# TSOC-USBUART1-3-1.net
KiCad netlist of a schematic drawn in EAGLE
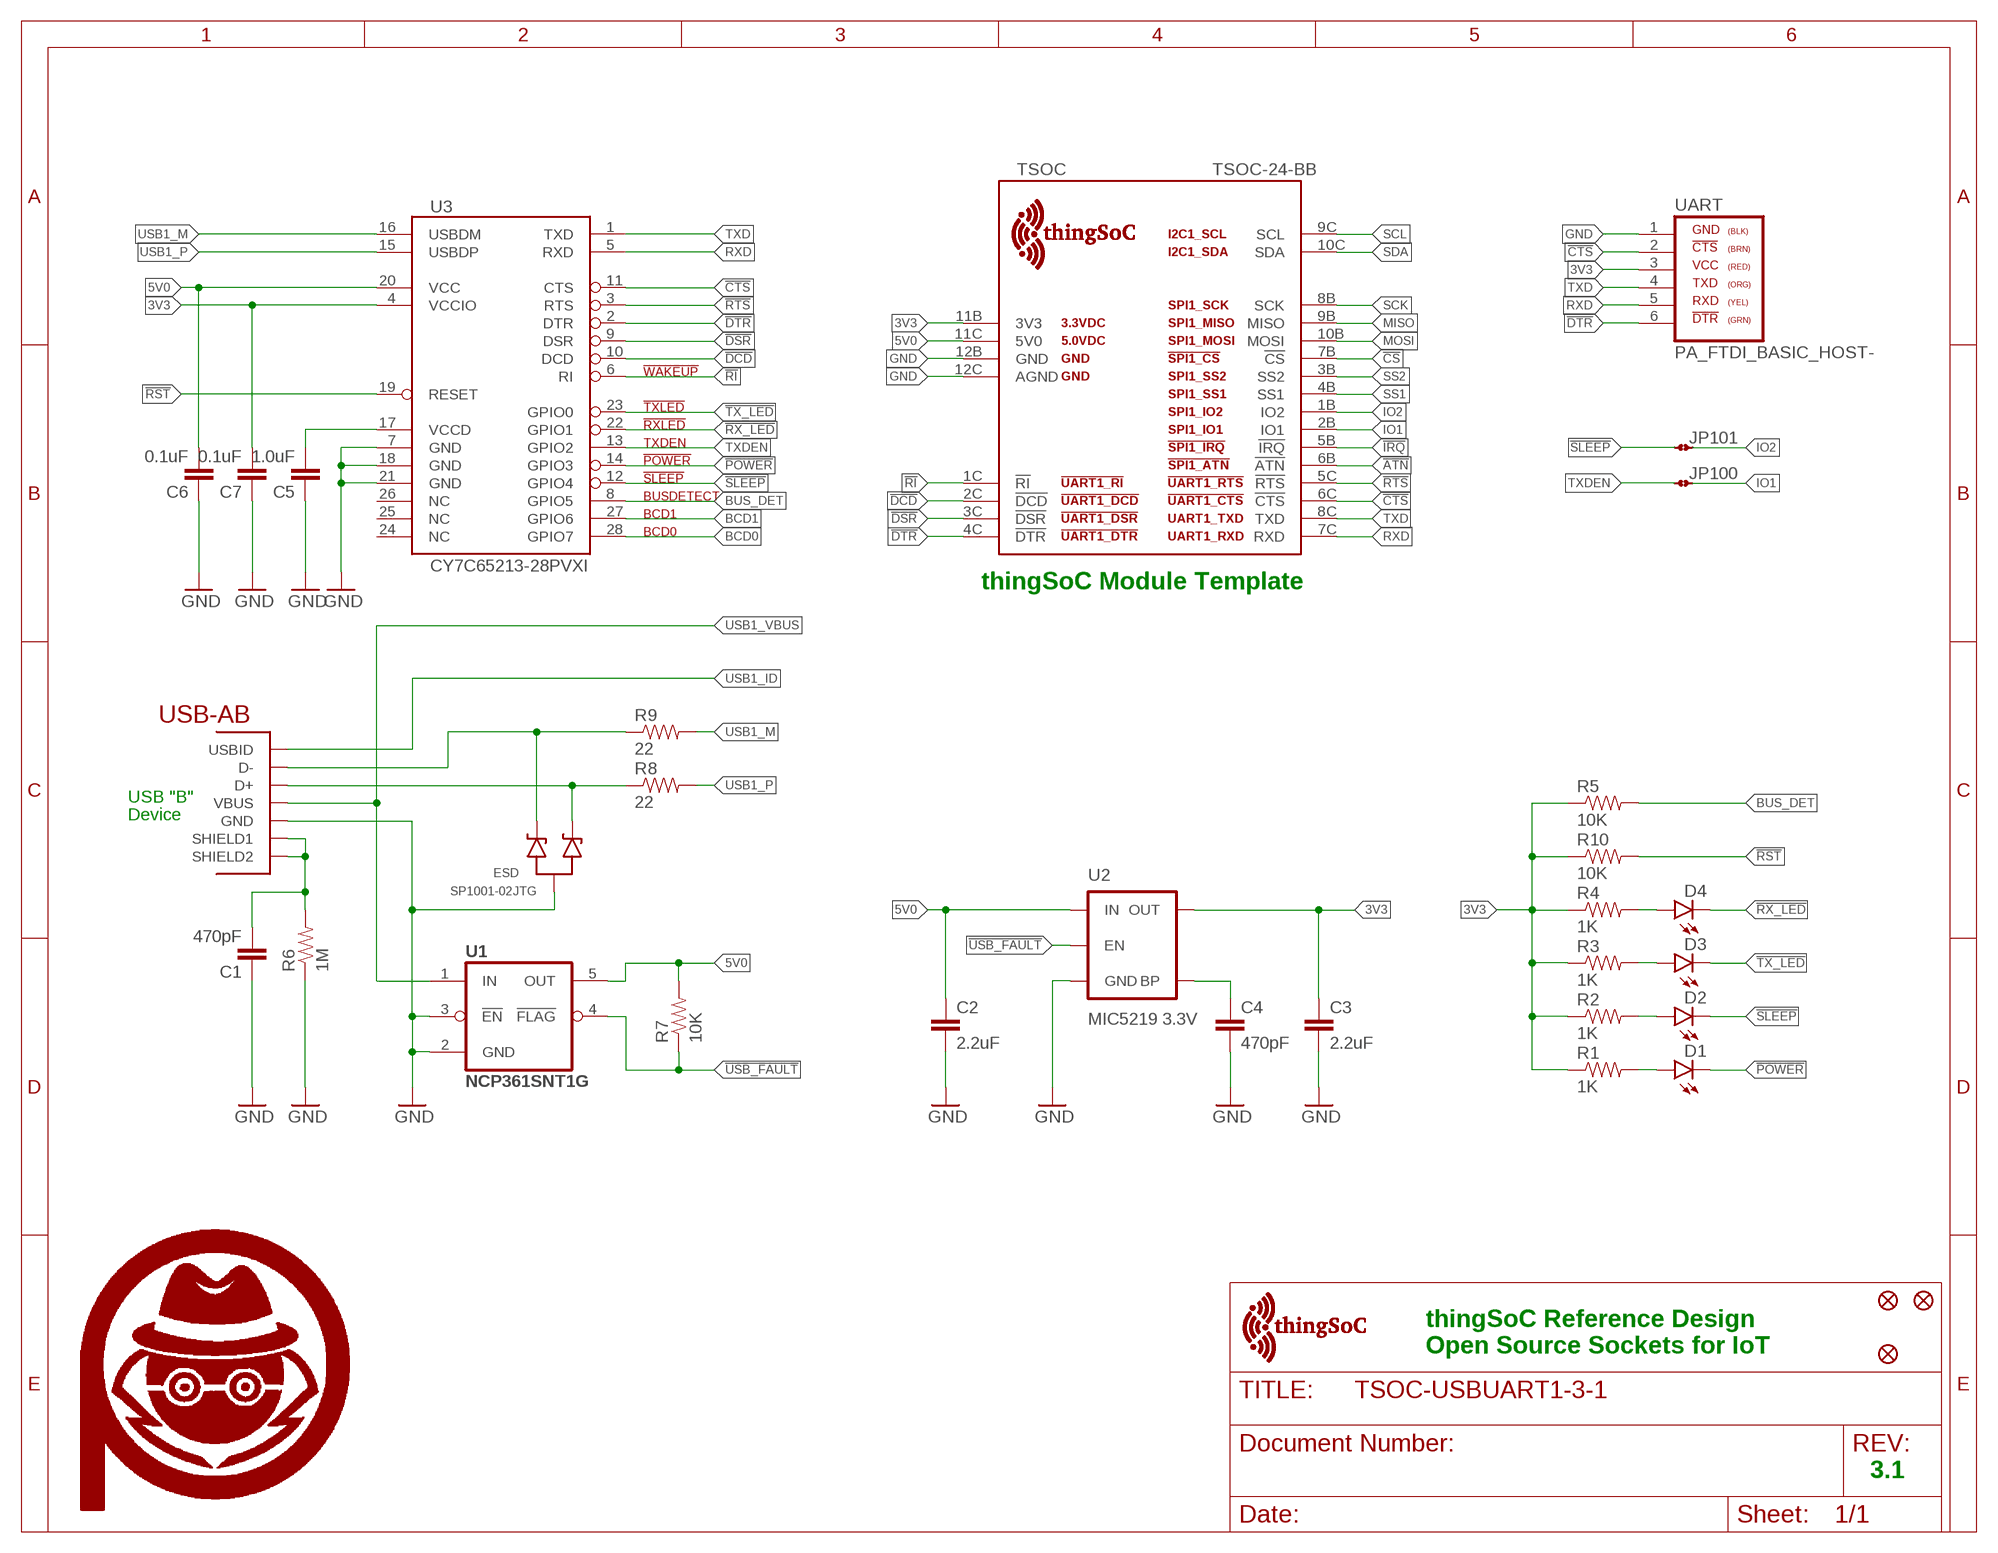
[diagram p0: schematic, sheet 1]

(export (version "E")
  (design (tool "Eeschema 10.0.6"))
  (components
    (comp (ref "C1")
      (value "470pF")
      (footprint "eagle-import:0603-CAP")
      (libsource (lib "eagle-import") (part "CAP0603-CAP"))
    )
    (comp (ref "C2")
      (value "2.2uF")
      (footprint "eagle-import:0603-CAP")
      (libsource (lib "eagle-import") (part "CAP0603-CAP"))
    )
    (comp (ref "C3")
      (value "2.2uF")
      (footprint "eagle-import:0603-CAP")
      (libsource (lib "eagle-import") (part "CAP0603-CAP"))
    )
    (comp (ref "C4")
      (value "470pF")
      (footprint "eagle-import:0603-CAP")
      (libsource (lib "eagle-import") (part "CAP0603-CAP"))
    )
    (comp (ref "C5")
      (value "1.0uF")
      (footprint "eagle-import:0603-CAP")
      (libsource (lib "eagle-import") (part "CAP0603-CAP"))
    )
    (comp (ref "C6")
      (value "0.1uF")
      (footprint "eagle-import:0603-CAP")
      (libsource (lib "eagle-import") (part "CAP0603-CAP"))
    )
    (comp (ref "C7")
      (value "0.1uF")
      (footprint "eagle-import:0603-CAP")
      (libsource (lib "eagle-import") (part "CAP0603-CAP"))
    )
    (comp (ref "D1")
      (value "LED0603")
      (footprint "eagle-import:LED-0603")
      (libsource (lib "eagle-import") (part "LED0603"))
    )
    (comp (ref "D2")
      (value "LED0603")
      (footprint "eagle-import:LED-0603")
      (libsource (lib "eagle-import") (part "LED0603"))
    )
    (comp (ref "D3")
      (value "LED0603")
      (footprint "eagle-import:LED-0603")
      (libsource (lib "eagle-import") (part "LED0603"))
    )
    (comp (ref "D4")
      (value "LED0603")
      (footprint "eagle-import:LED-0603")
      (libsource (lib "eagle-import") (part "LED0603"))
    )
    (comp (ref "ESD")
      (value "SP1001-02JTG")
      (footprint "eagle-import:SC70-3")
      (libsource (lib "eagle-import") (part "SP1001-02JTG"))
    )
    (comp (ref "FID1")
      (value "FIDUCIAL1.5X3")
      (footprint "eagle-import:FIDUCIAL-1.5X3")
      (libsource (lib "eagle-import") (part "FIDUCIAL1.5X3"))
    )
    (comp (ref "FID2")
      (value "FIDUCIAL1.5X3")
      (footprint "eagle-import:FIDUCIAL-1.5X3")
      (libsource (lib "eagle-import") (part "FIDUCIAL1.5X3"))
    )
    (comp (ref "FID3")
      (value "FIDUCIAL1.5X3")
      (footprint "eagle-import:FIDUCIAL-1.5X3")
      (libsource (lib "eagle-import") (part "FIDUCIAL1.5X3"))
    )
    (comp (ref "JP100")
      (value "JMP-2-NO")
      (footprint "eagle-import:JMP-2-NO")
      (libsource (lib "eagle-import") (part "JMP-2-NO"))
    )
    (comp (ref "JP101")
      (value "JMP-2-NO")
      (footprint "eagle-import:JMP-2-NO")
      (libsource (lib "eagle-import") (part "JMP-2-NO"))
    )
    (comp (ref "R1")
      (value "1K")
      (footprint "eagle-import:0603-RES")
      (libsource (lib "eagle-import") (part "RESISTOR0603-RES"))
    )
    (comp (ref "R2")
      (value "1K")
      (footprint "eagle-import:0603-RES")
      (libsource (lib "eagle-import") (part "RESISTOR0603-RES"))
    )
    (comp (ref "R3")
      (value "1K")
      (footprint "eagle-import:0603-RES")
      (libsource (lib "eagle-import") (part "RESISTOR0603-RES"))
    )
    (comp (ref "R4")
      (value "1K")
      (footprint "eagle-import:0603-RES")
      (libsource (lib "eagle-import") (part "RESISTOR0603-RES"))
    )
    (comp (ref "R5")
      (value "10K")
      (footprint "eagle-import:0603-RES")
      (libsource (lib "eagle-import") (part "RESISTOR0603-RES"))
    )
    (comp (ref "R6")
      (value "1M")
      (footprint "eagle-import:0603-RES")
      (libsource (lib "eagle-import") (part "RESISTOR0603-RES"))
    )
    (comp (ref "R7")
      (value "10K")
      (footprint "eagle-import:0603-RES")
      (libsource (lib "eagle-import") (part "RESISTOR0603-RES"))
    )
    (comp (ref "R8")
      (value "22")
      (footprint "eagle-import:0603-RES")
      (libsource (lib "eagle-import") (part "RESISTOR0603-RES"))
    )
    (comp (ref "R9")
      (value "22")
      (footprint "eagle-import:0603-RES")
      (libsource (lib "eagle-import") (part "RESISTOR0603-RES"))
    )
    (comp (ref "R10")
      (value "10K")
      (footprint "eagle-import:0603-RES")
      (libsource (lib "eagle-import") (part "RESISTOR0603-RES"))
    )
    (comp (ref "TSOC")
      (value "TSOC-24-BB")
      (footprint "eagle-import:TSOC-BB-S24")
      (libsource (lib "eagle-import") (part "TSOC-24-BB"))
    )
    (comp (ref "U$2")
      (value "TSOC-LOGO-MED")
      (footprint "eagle-import:TSOC-LOGO-MED")
      (libsource (lib "eagle-import") (part "TSOC-LOGO-MED"))
    )
    (comp (ref "U$3")
      (value "PA_LOGO_SYMMED")
      (footprint "eagle-import:PA_LOGO_AGENT_MED_SYM")
      (libsource (lib "eagle-import") (part "PA_LOGO_SYMMED"))
    )
    (comp (ref "U$100")
      (value "PA_LOGO_SYMMED")
      (footprint "eagle-import:PA_LOGO_AGENT_MED_SYM")
      (libsource (lib "eagle-import") (part "PA_LOGO_SYMMED"))
    )
    (comp (ref "U$101")
      (value "TSOC-LOGO-MED")
      (footprint "eagle-import:TSOC-LOGO-MED")
      (libsource (lib "eagle-import") (part "TSOC-LOGO-MED"))
    )
    (comp (ref "U1")
      (value "NCP361SNT1G")
      (footprint "eagle-import:SOP95P275X110-5N")
      (libsource (lib "eagle-import") (part "NCP361SNT1G"))
    )
    (comp (ref "U2")
      (value "MIC5219 3.3V")
      (footprint "eagle-import:SOT23-5")
      (libsource (lib "eagle-import") (part "V_REG_MIC52193.3V"))
    )
    (comp (ref "U3")
      (value "CY7C65213-28PVXI")
      (footprint "eagle-import:SSOP28DB")
      (libsource (lib "eagle-import") (part "CY7C65213-28PVXI"))
    )
    (comp (ref "UART")
      (value "PA_FTDI_BASIC_HOST-")
      (footprint "eagle-import:PA_FTDI_M5X1")
      (libsource (lib "eagle-import") (part "PA_FTDI_BASIC_HOST-"))
    )
    (comp (ref "USB1")
      (value "USB_AB")
      (footprint "eagle-import:USB-AB-MICRO-SMD")
      (libsource (lib "eagle-import") (part "USB_AB"))
    )
  )
  (nets
    (net (code "1") (name "/~{ATN}") (class "Default")
      (node (ref "TSOC") (pin "6B") (pinfunction "~{ATN}_6B") (pintype "bidirectional"))
    )
    (net (code "2") (name "/~{CS}") (class "Default")
      (node (ref "TSOC") (pin "7B") (pinfunction "~{CS}_7B") (pintype "bidirectional"))
    )
    (net (code "3") (name "/~{CTS}") (class "Default")
      (node (ref "TSOC") (pin "6C") (pinfunction "~{CTS}_6C") (pintype "bidirectional"))
      (node (ref "U3") (pin "11") (pinfunction "CTS_11") (pintype "input"))
      (node (ref "UART") (pin "2") (pinfunction "2_2") (pintype "passive"))
    )
    (net (code "4") (name "/~{DCD}") (class "Default")
      (node (ref "TSOC") (pin "2C") (pinfunction "~{DCD}_2C") (pintype "bidirectional"))
      (node (ref "U3") (pin "10") (pinfunction "DCD_10") (pintype "input"))
    )
    (net (code "5") (name "/~{DSR}") (class "Default")
      (node (ref "TSOC") (pin "3C") (pinfunction "~{DSR}_3C") (pintype "bidirectional"))
      (node (ref "U3") (pin "9") (pinfunction "DSR_9") (pintype "input"))
    )
    (net (code "6") (name "/~{DTR}") (class "Default")
      (node (ref "TSOC") (pin "4C") (pinfunction "~{DTR}_4C") (pintype "bidirectional"))
      (node (ref "U3") (pin "2") (pinfunction "DTR_2") (pintype "output"))
      (node (ref "UART") (pin "6") (pinfunction "6_6") (pintype "passive"))
    )
    (net (code "7") (name "/~{IRQ}") (class "Default")
      (node (ref "TSOC") (pin "5B") (pinfunction "~{IRQ}_5B") (pintype "bidirectional"))
    )
    (net (code "8") (name "/~{POWER}") (class "Default")
      (node (ref "D1") (pin "C") (pinfunction "C_C") (pintype "passive"))
      (node (ref "U3") (pin "14") (pinfunction "GPIO3_14") (pintype "output"))
    )
    (net (code "9") (name "/~{RI}") (class "Default")
      (node (ref "TSOC") (pin "1C") (pinfunction "~{RI}_1C") (pintype "bidirectional"))
      (node (ref "U3") (pin "6") (pinfunction "RI_6") (pintype "input"))
    )
    (net (code "10") (name "/~{RST}") (class "Default")
      (node (ref "R10") (pin "2") (pinfunction "2_2") (pintype "passive"))
      (node (ref "U3") (pin "19") (pinfunction "RESET_19") (pintype "input"))
    )
    (net (code "11") (name "/~{RTS}") (class "Default")
      (node (ref "TSOC") (pin "5C") (pinfunction "~{RTS}_5C") (pintype "bidirectional"))
      (node (ref "U3") (pin "3") (pinfunction "RTS_3") (pintype "output"))
    )
    (net (code "12") (name "/~{RX_LED}") (class "Default")
      (node (ref "D4") (pin "C") (pinfunction "C_C") (pintype "passive"))
      (node (ref "U3") (pin "22") (pinfunction "GPIO1_22") (pintype "output"))
    )
    (net (code "13") (name "/~{SLEEP}") (class "Default")
      (node (ref "D2") (pin "C") (pinfunction "C_C") (pintype "passive"))
      (node (ref "JP101") (pin "1") (pinfunction "1_1") (pintype "passive"))
      (node (ref "U3") (pin "12") (pinfunction "GPIO4_12") (pintype "input"))
    )
    (net (code "14") (name "/~{TX_LED}") (class "Default")
      (node (ref "D3") (pin "C") (pinfunction "C_C") (pintype "passive"))
      (node (ref "U3") (pin "23") (pinfunction "GPIO0_23") (pintype "output"))
    )
    (net (code "15") (name "/~{USB_FAULT}") (class "Default")
      (node (ref "R7") (pin "1") (pinfunction "1_1") (pintype "passive"))
      (node (ref "U1") (pin "4") (pinfunction "~{FLAG}_4") (pintype "input"))
      (node (ref "U2") (pin "3") (pinfunction "EN_3") (pintype "input"))
    )
    (net (code "16") (name "3V3") (class "Default")
      (node (ref "C3") (pin "1") (pinfunction "1_1") (pintype "passive"))
      (node (ref "C7") (pin "2") (pinfunction "2_2") (pintype "passive"))
      (node (ref "R1") (pin "1") (pinfunction "1_1") (pintype "passive"))
      (node (ref "R10") (pin "1") (pinfunction "1_1") (pintype "passive"))
      (node (ref "R2") (pin "1") (pinfunction "1_1") (pintype "passive"))
      (node (ref "R3") (pin "1") (pinfunction "1_1") (pintype "passive"))
      (node (ref "R4") (pin "1") (pinfunction "1_1") (pintype "passive"))
      (node (ref "R5") (pin "1") (pinfunction "1_1") (pintype "passive"))
      (node (ref "TSOC") (pin "11B") (pinfunction "3V3_11B") (pintype "bidirectional"))
      (node (ref "U2") (pin "5") (pinfunction "OUT_5") (pintype "passive"))
      (node (ref "U3") (pin "4") (pinfunction "VCCIO_4") (pintype "power_in"))
      (node (ref "UART") (pin "3") (pinfunction "3_3") (pintype "passive"))
    )
    (net (code "17") (name "5V0") (class "Default")
      (node (ref "C2") (pin "1") (pinfunction "1_1") (pintype "passive"))
      (node (ref "C6") (pin "2") (pinfunction "2_2") (pintype "passive"))
      (node (ref "R7") (pin "2") (pinfunction "2_2") (pintype "passive"))
      (node (ref "TSOC") (pin "11C") (pinfunction "5V0_11C") (pintype "bidirectional"))
      (node (ref "U1") (pin "5") (pinfunction "OUT_5") (pintype "output"))
      (node (ref "U2") (pin "1") (pinfunction "IN_1") (pintype "input"))
      (node (ref "U3") (pin "20") (pinfunction "VCC_20") (pintype "power_in"))
    )
    (net (code "18") (name "BCD0") (class "Default")
      (node (ref "U3") (pin "28") (pinfunction "GPIO7_28") (pintype "output"))
    )
    (net (code "19") (name "BCD1") (class "Default")
      (node (ref "U3") (pin "27") (pinfunction "GPIO6_27") (pintype "output"))
    )
    (net (code "20") (name "BUS_DET") (class "Default")
      (node (ref "R5") (pin "2") (pinfunction "2_2") (pintype "passive"))
      (node (ref "U3") (pin "8") (pinfunction "GPIO5_8") (pintype "input"))
    )
    (net (code "21") (name "GND") (class "Default")
      (node (ref "C1") (pin "1") (pinfunction "1_1") (pintype "passive"))
      (node (ref "C2") (pin "2") (pinfunction "2_2") (pintype "passive"))
      (node (ref "C3") (pin "2") (pinfunction "2_2") (pintype "passive"))
      (node (ref "C4") (pin "2") (pinfunction "2_2") (pintype "passive"))
      (node (ref "C5") (pin "1") (pinfunction "1_1") (pintype "passive"))
      (node (ref "C6") (pin "1") (pinfunction "1_1") (pintype "passive"))
      (node (ref "C7") (pin "1") (pinfunction "1_1") (pintype "passive"))
      (node (ref "ESD") (pin "3") (pinfunction "A_3") (pintype "passive"))
      (node (ref "R6") (pin "1") (pinfunction "1_1") (pintype "passive"))
      (node (ref "TSOC") (pin "12B") (pinfunction "GND_12B") (pintype "bidirectional"))
      (node (ref "TSOC") (pin "12C") (pinfunction "AGND_12C") (pintype "bidirectional"))
      (node (ref "U1") (pin "2") (pinfunction "GND_2") (pintype "passive"))
      (node (ref "U1") (pin "3") (pinfunction "~{EN}_3") (pintype "input"))
      (node (ref "U2") (pin "2") (pinfunction "GND_2") (pintype "input"))
      (node (ref "U3") (pin "18") (pinfunction "GND_18") (pintype "power_in"))
      (node (ref "U3") (pin "21") (pinfunction "GND_21") (pintype "power_in"))
      (node (ref "U3") (pin "7") (pinfunction "GND_7") (pintype "power_in"))
      (node (ref "UART") (pin "1") (pinfunction "1_1") (pintype "passive"))
      (node (ref "USB1") (pin "GND") (pinfunction "GND_GND") (pintype "bidirectional"))
    )
    (net (code "22") (name "IO1") (class "Default")
      (node (ref "JP100") (pin "2") (pinfunction "2_2") (pintype "passive"))
      (node (ref "TSOC") (pin "2B") (pinfunction "IO1_2B") (pintype "bidirectional"))
    )
    (net (code "23") (name "IO2") (class "Default")
      (node (ref "JP101") (pin "2") (pinfunction "2_2") (pintype "passive"))
      (node (ref "TSOC") (pin "1B") (pinfunction "IO2_1B") (pintype "bidirectional"))
    )
    (net (code "24") (name "MISO") (class "Default")
      (node (ref "TSOC") (pin "9B") (pinfunction "MISO_9B") (pintype "bidirectional"))
    )
    (net (code "25") (name "MOSI") (class "Default")
      (node (ref "TSOC") (pin "10B") (pinfunction "MOSI_10B") (pintype "bidirectional"))
    )
    (net (code "26") (name "Net-(C1-Pad2)") (class "Default")
      (node (ref "C1") (pin "2") (pinfunction "2_2") (pintype "passive"))
      (node (ref "R6") (pin "2") (pinfunction "2_2") (pintype "passive"))
      (node (ref "USB1") (pin "SHIELD1") (pinfunction "SHIELD1_SHIELD1") (pintype "bidirectional"))
      (node (ref "USB1") (pin "SHIELD2") (pinfunction "SHIELD2_SHIELD2") (pintype "bidirectional"))
    )
    (net (code "27") (name "Net-(D1-PadA)") (class "Default")
      (node (ref "D1") (pin "A") (pinfunction "A_A") (pintype "passive"))
      (node (ref "R1") (pin "2") (pinfunction "2_2") (pintype "passive"))
    )
    (net (code "28") (name "Net-(D2-PadA)") (class "Default")
      (node (ref "D2") (pin "A") (pinfunction "A_A") (pintype "passive"))
      (node (ref "R2") (pin "2") (pinfunction "2_2") (pintype "passive"))
    )
    (net (code "29") (name "Net-(D3-PadA)") (class "Default")
      (node (ref "D3") (pin "A") (pinfunction "A_A") (pintype "passive"))
      (node (ref "R3") (pin "2") (pinfunction "2_2") (pintype "passive"))
    )
    (net (code "30") (name "Net-(D4-PadA)") (class "Default")
      (node (ref "D4") (pin "A") (pinfunction "A_A") (pintype "passive"))
      (node (ref "R4") (pin "2") (pinfunction "2_2") (pintype "passive"))
    )
    (net (code "31") (name "Net-(ESD-C1)") (class "Default")
      (node (ref "ESD") (pin "1") (pinfunction "C1_1") (pintype "passive"))
      (node (ref "R8") (pin "1") (pinfunction "1_1") (pintype "passive"))
      (node (ref "USB1") (pin "D+") (pinfunction "D+_D+") (pintype "bidirectional"))
    )
    (net (code "32") (name "Net-(ESD-C2)") (class "Default")
      (node (ref "ESD") (pin "2") (pinfunction "C2_2") (pintype "passive"))
      (node (ref "R9") (pin "1") (pinfunction "1_1") (pintype "passive"))
      (node (ref "USB1") (pin "D-") (pinfunction "D-_D-") (pintype "bidirectional"))
    )
    (net (code "33") (name "Net-(U2-BP)") (class "Default")
      (node (ref "C4") (pin "1") (pinfunction "1_1") (pintype "passive"))
      (node (ref "U2") (pin "4") (pinfunction "BP_4") (pintype "input"))
    )
    (net (code "34") (name "Net-(U3-VCCD)") (class "Default")
      (node (ref "C5") (pin "2") (pinfunction "2_2") (pintype "passive"))
      (node (ref "U3") (pin "17") (pinfunction "VCCD_17") (pintype "power_in"))
    )
    (net (code "35") (name "RXD") (class "Default")
      (node (ref "TSOC") (pin "7C") (pinfunction "RXD_7C") (pintype "bidirectional"))
      (node (ref "U3") (pin "5") (pinfunction "RXD_5") (pintype "input"))
      (node (ref "UART") (pin "5") (pinfunction "5_5") (pintype "passive"))
    )
    (net (code "36") (name "SCK") (class "Default")
      (node (ref "TSOC") (pin "8B") (pinfunction "SCK_8B") (pintype "bidirectional"))
    )
    (net (code "37") (name "SCL") (class "Default")
      (node (ref "TSOC") (pin "9C") (pinfunction "SCL_9C") (pintype "bidirectional"))
    )
    (net (code "38") (name "SDA") (class "Default")
      (node (ref "TSOC") (pin "10C") (pinfunction "SDA_10C") (pintype "bidirectional"))
    )
    (net (code "39") (name "SS1") (class "Default")
      (node (ref "TSOC") (pin "4B") (pinfunction "SS1_4B") (pintype "bidirectional"))
    )
    (net (code "40") (name "SS2") (class "Default")
      (node (ref "TSOC") (pin "3B") (pinfunction "SS2_3B") (pintype "bidirectional"))
    )
    (net (code "41") (name "TXD") (class "Default")
      (node (ref "TSOC") (pin "8C") (pinfunction "TXD_8C") (pintype "bidirectional"))
      (node (ref "U3") (pin "1") (pinfunction "TXD_1") (pintype "output"))
      (node (ref "UART") (pin "4") (pinfunction "4_4") (pintype "passive"))
    )
    (net (code "42") (name "TXDEN") (class "Default")
      (node (ref "JP100") (pin "1") (pinfunction "1_1") (pintype "passive"))
      (node (ref "U3") (pin "13") (pinfunction "GPIO2_13") (pintype "output"))
    )
    (net (code "43") (name "USB1_ID") (class "Default")
      (node (ref "USB1") (pin "ID") (pinfunction "USBID_ID") (pintype "bidirectional"))
    )
    (net (code "44") (name "USB1_M") (class "Default")
      (node (ref "R9") (pin "2") (pinfunction "2_2") (pintype "passive"))
      (node (ref "U3") (pin "16") (pinfunction "USBDM_16") (pintype "bidirectional"))
    )
    (net (code "45") (name "USB1_P") (class "Default")
      (node (ref "R8") (pin "2") (pinfunction "2_2") (pintype "passive"))
      (node (ref "U3") (pin "15") (pinfunction "USBDP_15") (pintype "bidirectional"))
    )
    (net (code "46") (name "USB1_VBUS") (class "Default")
      (node (ref "U1") (pin "1") (pinfunction "IN_1") (pintype "power_in"))
      (node (ref "USB1") (pin "VBUS") (pinfunction "VBUS_VBUS") (pintype "bidirectional"))
    )
    (net (code "47") (name "unconnected-(U3-NC-Pad24)") (class "Default")
      (node (ref "U3") (pin "24") (pinfunction "NC_24") (pintype "no_connect"))
    )
    (net (code "48") (name "unconnected-(U3-NC-Pad25)") (class "Default")
      (node (ref "U3") (pin "25") (pinfunction "NC_25") (pintype "no_connect"))
    )
    (net (code "49") (name "unconnected-(U3-NC-Pad26)") (class "Default")
      (node (ref "U3") (pin "26") (pinfunction "NC_26") (pintype "no_connect"))
    )
  )
)
